# POVD-2.net
KiCad netlist of a schematic drawn in EAGLE
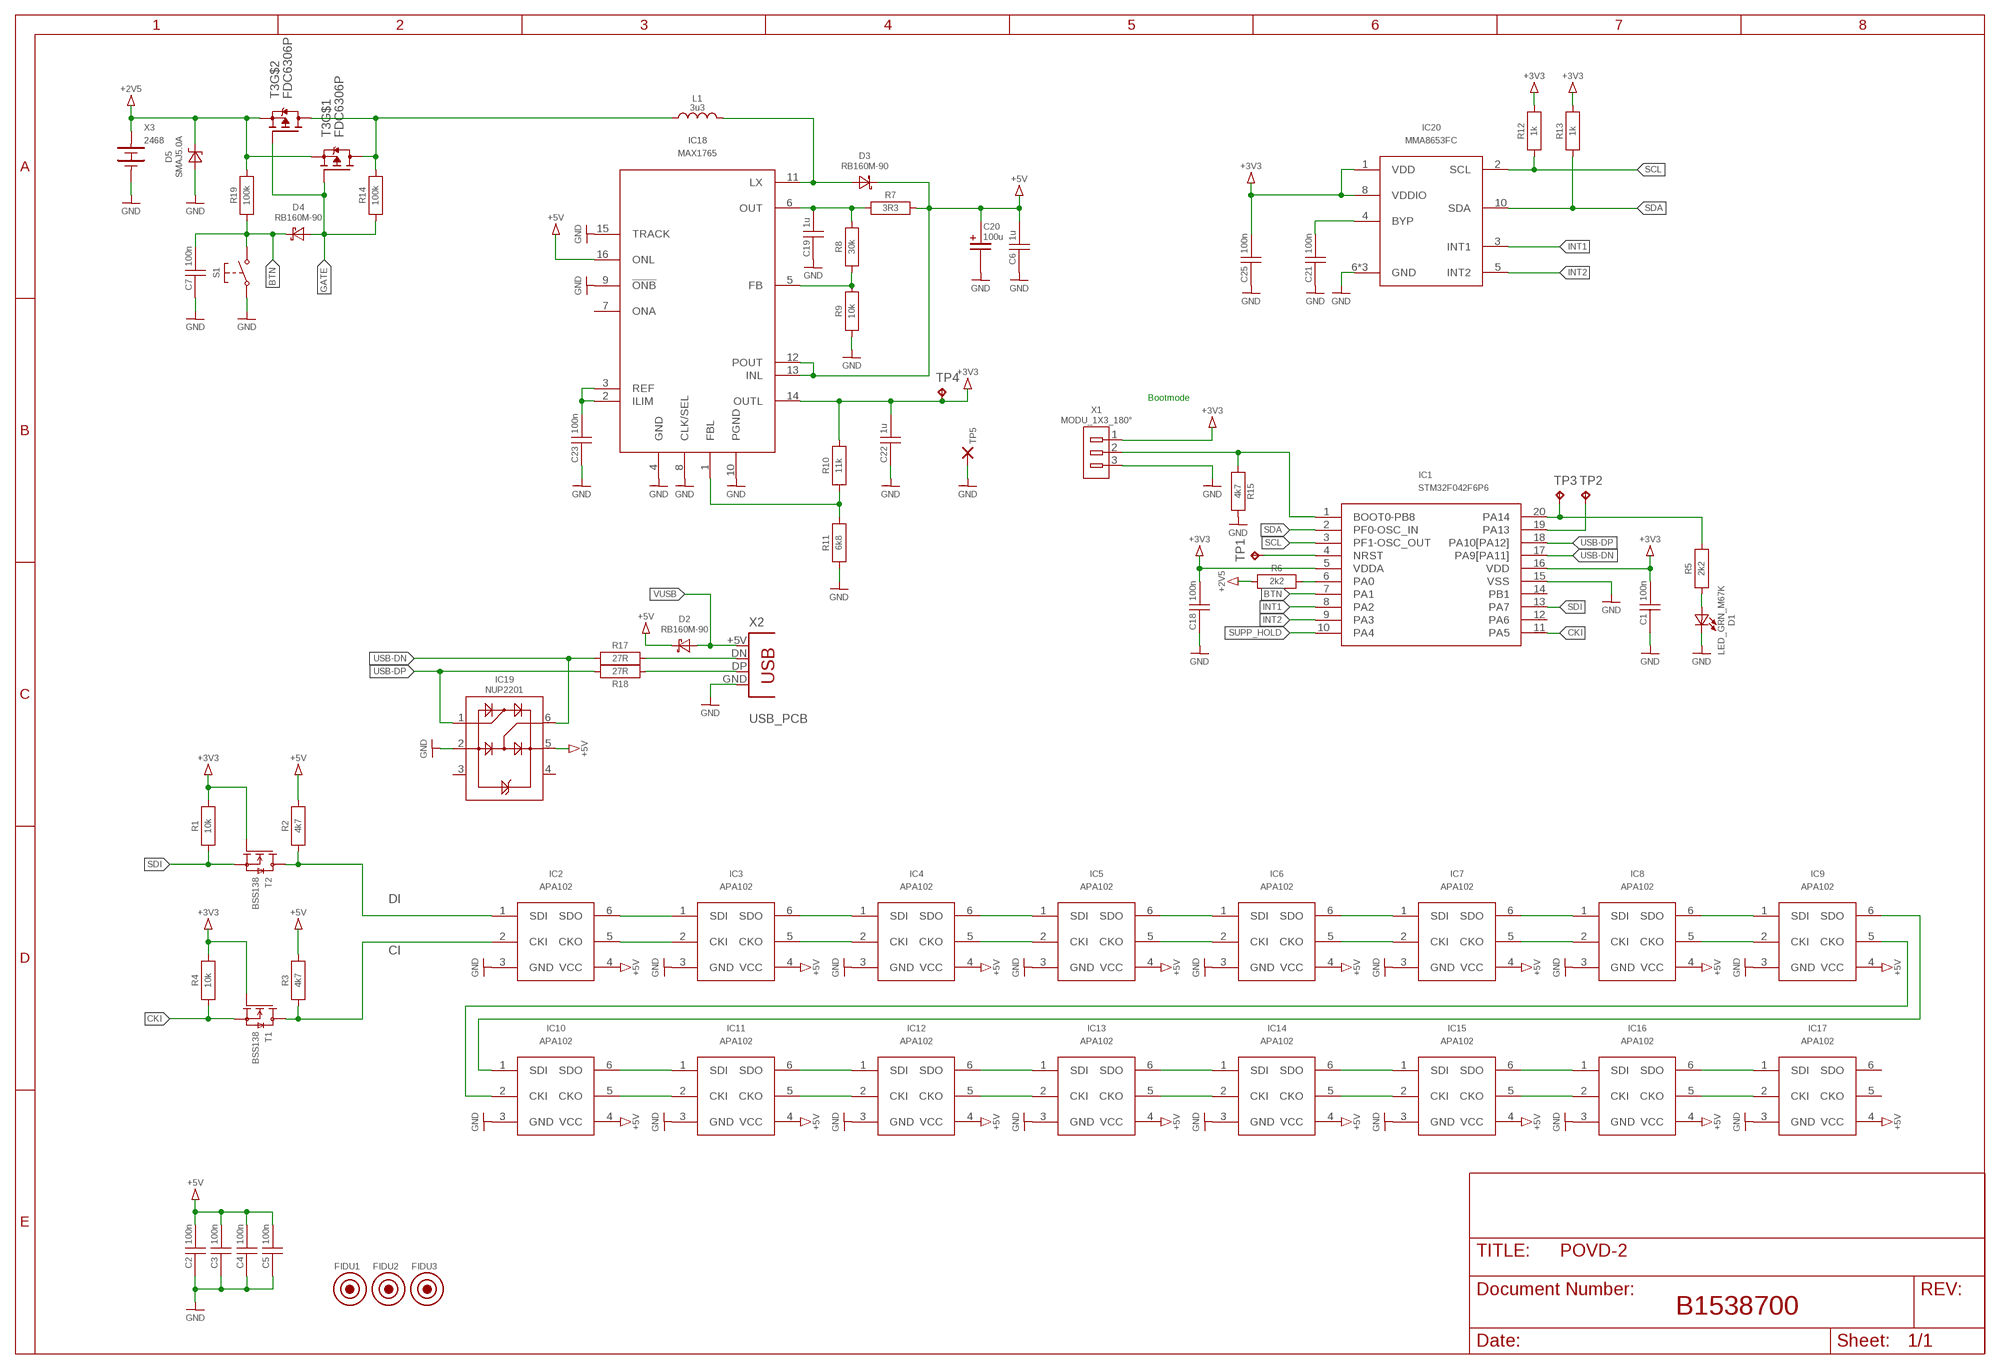
[diagram p0: schematic, sheet 1]

(export (version "E")
  (design (tool "Eeschema 10.0.6"))
  (components
    (comp (ref "C1")
      (value "100n")
      (footprint "eagle-import:SM_1206")
      (fields (field (name "PARTNR") "E0001400"))
      (libsource (lib "eagle-import") (part "C1206"))
    )
    (comp (ref "C2")
      (value "100n")
      (footprint "eagle-import:SM_1206")
      (fields (field (name "PARTNR") "E0001400"))
      (libsource (lib "eagle-import") (part "C1206"))
    )
    (comp (ref "C3")
      (value "100n")
      (footprint "eagle-import:SM_1206")
      (fields (field (name "PARTNR") "E0001400"))
      (libsource (lib "eagle-import") (part "C1206"))
    )
    (comp (ref "C4")
      (value "100n")
      (footprint "eagle-import:SM_1206")
      (fields (field (name "PARTNR") "E0001400"))
      (libsource (lib "eagle-import") (part "C1206"))
    )
    (comp (ref "C5")
      (value "100n")
      (footprint "eagle-import:SM_1206")
      (fields (field (name "PARTNR") "E0001400"))
      (libsource (lib "eagle-import") (part "C1206"))
    )
    (comp (ref "C6")
      (value "1u")
      (footprint "eagle-import:SM_1206")
      (fields (field (name "PARTNR") "E0487200"))
      (libsource (lib "eagle-import") (part "C1206"))
    )
    (comp (ref "C7")
      (value "100n")
      (footprint "eagle-import:SM_1206")
      (fields (field (name "PARTNR") "E0001400"))
      (libsource (lib "eagle-import") (part "C1206"))
    )
    (comp (ref "C18")
      (value "100n")
      (footprint "eagle-import:SM_1206")
      (fields (field (name "PARTNR") "E0001400"))
      (libsource (lib "eagle-import") (part "C1206"))
    )
    (comp (ref "C19")
      (value "1u")
      (footprint "eagle-import:SM_1206")
      (fields (field (name "PARTNR") "E0487200"))
      (libsource (lib "eagle-import") (part "C1206"))
    )
    (comp (ref "C20")
      (value "100u")
      (footprint "eagle-import:SM_SIZE-D")
      (fields (field (name "PARTNR") "E0242200"))
      (libsource (lib "eagle-import") (part "CPOLSIZE-D"))
    )
    (comp (ref "C21")
      (value "100n")
      (footprint "eagle-import:SM_1206")
      (fields (field (name "PARTNR") "E0001400"))
      (libsource (lib "eagle-import") (part "C1206"))
    )
    (comp (ref "C22")
      (value "1u")
      (footprint "eagle-import:SM_1206")
      (fields (field (name "PARTNR") "E0487200"))
      (libsource (lib "eagle-import") (part "C1206"))
    )
    (comp (ref "C23")
      (value "100n")
      (footprint "eagle-import:SM_1206")
      (fields (field (name "PARTNR") "E0001400"))
      (libsource (lib "eagle-import") (part "C1206"))
    )
    (comp (ref "C25")
      (value "100n")
      (footprint "eagle-import:SM_1206")
      (fields (field (name "PARTNR") "E0001400"))
      (libsource (lib "eagle-import") (part "C1206"))
    )
    (comp (ref "D1")
      (value "LED_GRN_M67K")
      (footprint "eagle-import:SM_LED_M67K")
      (libsource (lib "eagle-import") (part "LED_M67K_GRN"))
    )
    (comp (ref "D2")
      (value "RB160M-90")
      (footprint "eagle-import:SM_SOD123_POL")
      (libsource (lib "eagle-import") (part "RB160M-90"))
    )
    (comp (ref "D3")
      (value "RB160M-90")
      (footprint "eagle-import:SM_SOD123_POL")
      (libsource (lib "eagle-import") (part "RB160M-90"))
    )
    (comp (ref "D4")
      (value "RB160M-90")
      (footprint "eagle-import:SM_SOD123_POL")
      (libsource (lib "eagle-import") (part "RB160M-90"))
    )
    (comp (ref "D5")
      (value "SMAJ5.0A")
      (footprint "eagle-import:SM_DO214AC_POL")
      (libsource (lib "eagle-import") (part "SMAJA5.0"))
    )
    (comp (ref "FIDU1")
      (value "FIDU_ROUND_NEW")
      (footprint "eagle-import:FIDUCIAL_LOETSTOPP")
      (libsource (lib "eagle-import") (part "FIDU_ROUND_NEW"))
    )
    (comp (ref "FIDU2")
      (value "FIDU_ROUND_NEW")
      (footprint "eagle-import:FIDUCIAL_LOETSTOPP")
      (libsource (lib "eagle-import") (part "FIDU_ROUND_NEW"))
    )
    (comp (ref "FIDU3")
      (value "FIDU_ROUND_NEW")
      (footprint "eagle-import:FIDUCIAL_LOETSTOPP")
      (libsource (lib "eagle-import") (part "FIDU_ROUND_NEW"))
    )
    (comp (ref "IC1")
      (value "STM32F042F6P6")
      (footprint "eagle-import:SM_TSSOP20")
      (libsource (lib "eagle-import") (part "STM32F042F6P6"))
    )
    (comp (ref "IC2")
      (value "APA102")
      (footprint "eagle-import:SM_LED_PLCC6")
      (libsource (lib "eagle-import") (part "APA102"))
    )
    (comp (ref "IC3")
      (value "APA102")
      (footprint "eagle-import:SM_LED_PLCC6")
      (libsource (lib "eagle-import") (part "APA102"))
    )
    (comp (ref "IC4")
      (value "APA102")
      (footprint "eagle-import:SM_LED_PLCC6")
      (libsource (lib "eagle-import") (part "APA102"))
    )
    (comp (ref "IC5")
      (value "APA102")
      (footprint "eagle-import:SM_LED_PLCC6")
      (libsource (lib "eagle-import") (part "APA102"))
    )
    (comp (ref "IC6")
      (value "APA102")
      (footprint "eagle-import:SM_LED_PLCC6")
      (libsource (lib "eagle-import") (part "APA102"))
    )
    (comp (ref "IC7")
      (value "APA102")
      (footprint "eagle-import:SM_LED_PLCC6")
      (libsource (lib "eagle-import") (part "APA102"))
    )
    (comp (ref "IC8")
      (value "APA102")
      (footprint "eagle-import:SM_LED_PLCC6")
      (libsource (lib "eagle-import") (part "APA102"))
    )
    (comp (ref "IC9")
      (value "APA102")
      (footprint "eagle-import:SM_LED_PLCC6")
      (libsource (lib "eagle-import") (part "APA102"))
    )
    (comp (ref "IC10")
      (value "APA102")
      (footprint "eagle-import:SM_LED_PLCC6")
      (libsource (lib "eagle-import") (part "APA102"))
    )
    (comp (ref "IC11")
      (value "APA102")
      (footprint "eagle-import:SM_LED_PLCC6")
      (libsource (lib "eagle-import") (part "APA102"))
    )
    (comp (ref "IC12")
      (value "APA102")
      (footprint "eagle-import:SM_LED_PLCC6")
      (libsource (lib "eagle-import") (part "APA102"))
    )
    (comp (ref "IC13")
      (value "APA102")
      (footprint "eagle-import:SM_LED_PLCC6")
      (libsource (lib "eagle-import") (part "APA102"))
    )
    (comp (ref "IC14")
      (value "APA102")
      (footprint "eagle-import:SM_LED_PLCC6")
      (libsource (lib "eagle-import") (part "APA102"))
    )
    (comp (ref "IC15")
      (value "APA102")
      (footprint "eagle-import:SM_LED_PLCC6")
      (libsource (lib "eagle-import") (part "APA102"))
    )
    (comp (ref "IC16")
      (value "APA102")
      (footprint "eagle-import:SM_LED_PLCC6")
      (libsource (lib "eagle-import") (part "APA102"))
    )
    (comp (ref "IC17")
      (value "APA102")
      (footprint "eagle-import:SM_LED_PLCC6")
      (libsource (lib "eagle-import") (part "APA102"))
    )
    (comp (ref "IC18")
      (value "MAX1765")
      (footprint "eagle-import:SM_QSOP16")
      (libsource (lib "eagle-import") (part "MAX1765"))
    )
    (comp (ref "IC19")
      (value "NUP2201")
      (footprint "eagle-import:TSOP6")
      (libsource (lib "eagle-import") (part "NUP2201"))
    )
    (comp (ref "IC20")
      (value "MMA8653FC")
      (footprint "eagle-import:SM_DFN10")
      (libsource (lib "eagle-import") (part "MMA8653FC"))
    )
    (comp (ref "L1")
      (value "3u3")
      (footprint "eagle-import:SM_L_MOS6020")
      (libsource (lib "eagle-import") (part "L_MOS6020"))
    )
    (comp (ref "R1")
      (value "10k")
      (footprint "eagle-import:SM_1206")
      (fields (field (name "PARTNR") "E0002700"))
      (libsource (lib "eagle-import") (part "R1206"))
    )
    (comp (ref "R2")
      (value "4k7")
      (footprint "eagle-import:SM_1206")
      (fields (field (name "PARTNR") "E0002200"))
      (libsource (lib "eagle-import") (part "R1206"))
    )
    (comp (ref "R3")
      (value "4k7")
      (footprint "eagle-import:SM_1206")
      (fields (field (name "PARTNR") "E0002200"))
      (libsource (lib "eagle-import") (part "R1206"))
    )
    (comp (ref "R4")
      (value "10k")
      (footprint "eagle-import:SM_1206")
      (fields (field (name "PARTNR") "E0002700"))
      (libsource (lib "eagle-import") (part "R1206"))
    )
    (comp (ref "R5")
      (value "2k2")
      (footprint "eagle-import:SM_1206")
      (fields (field (name "PARTNR") "E0066600"))
      (libsource (lib "eagle-import") (part "R1206"))
    )
    (comp (ref "R6")
      (value "2k2")
      (footprint "eagle-import:SM_1206")
      (fields (field (name "PARTNR") "E0066600"))
      (libsource (lib "eagle-import") (part "R1206"))
    )
    (comp (ref "R7")
      (value "3R3")
      (footprint "eagle-import:SM_1206")
      (fields (field (name "PARTNR") "E0821300"))
      (libsource (lib "eagle-import") (part "R1206"))
    )
    (comp (ref "R8")
      (value "30k")
      (footprint "eagle-import:SM_1206")
      (libsource (lib "eagle-import") (part "R1206"))
    )
    (comp (ref "R9")
      (value "10k")
      (footprint "eagle-import:SM_1206")
      (fields (field (name "PARTNR") "E0002700"))
      (libsource (lib "eagle-import") (part "R1206"))
    )
    (comp (ref "R10")
      (value "11k")
      (footprint "eagle-import:SM_1206")
      (libsource (lib "eagle-import") (part "R1206"))
    )
    (comp (ref "R11")
      (value "6k8")
      (footprint "eagle-import:SM_1206")
      (fields (field (name "PARTNR") "E0195100"))
      (libsource (lib "eagle-import") (part "R1206"))
    )
    (comp (ref "R12")
      (value "1k")
      (footprint "eagle-import:SM_1206")
      (fields (field (name "PARTNR") "E0002500"))
      (libsource (lib "eagle-import") (part "R1206"))
    )
    (comp (ref "R13")
      (value "1k")
      (footprint "eagle-import:SM_1206")
      (fields (field (name "PARTNR") "E0002500"))
      (libsource (lib "eagle-import") (part "R1206"))
    )
    (comp (ref "R14")
      (value "100k")
      (footprint "eagle-import:SM_1206")
      (fields (field (name "PARTNR") "E0002800"))
      (libsource (lib "eagle-import") (part "R1206"))
    )
    (comp (ref "R15")
      (value "4k7")
      (footprint "eagle-import:SM_1206")
      (fields (field (name "PARTNR") "E0002200"))
      (libsource (lib "eagle-import") (part "R1206"))
    )
    (comp (ref "R17")
      (value "27R")
      (footprint "eagle-import:SM_1206")
      (fields (field (name "PARTNR") "E0023100"))
      (libsource (lib "eagle-import") (part "R1206"))
    )
    (comp (ref "R18")
      (value "27R")
      (footprint "eagle-import:SM_1206")
      (fields (field (name "PARTNR") "E0023100"))
      (libsource (lib "eagle-import") (part "R1206"))
    )
    (comp (ref "R19")
      (value "100k")
      (footprint "eagle-import:SM_1206")
      (fields (field (name "PARTNR") "E0002800"))
      (libsource (lib "eagle-import") (part "R1206"))
    )
    (comp (ref "S1")
      (value "PUSH-BUTTON_SMD")
      (footprint "eagle-import:PUSH-BUTTON_SMD")
      (libsource (lib "eagle-import") (part "PUSH-BUTTON_SMD"))
    )
    (comp (ref "T1")
      (value "BSS138")
      (footprint "eagle-import:SM_SOT23")
      (libsource (lib "eagle-import") (part "BSS138"))
    )
    (comp (ref "T2")
      (value "BSS138")
      (footprint "eagle-import:SM_SOT23")
      (libsource (lib "eagle-import") (part "BSS138"))
    )
    (comp (ref "T3")
      (value "FDC6306P")
      (footprint "eagle-import:TSOP6")
      (fields (field (name "PARTNR") "E0662100"))
      (libsource (lib "eagle-import") (part "FDC6306P"))
    )
    (comp (ref "TP1")
      (value "TPTP12R")
      (footprint "eagle-import:TP12R")
      (libsource (lib "eagle-import") (part "TPTP12R"))
    )
    (comp (ref "TP2")
      (value "TPTP12R")
      (footprint "eagle-import:TP12R")
      (libsource (lib "eagle-import") (part "TPTP12R"))
    )
    (comp (ref "TP3")
      (value "TPTP12R")
      (footprint "eagle-import:TP12R")
      (libsource (lib "eagle-import") (part "TPTP12R"))
    )
    (comp (ref "TP4")
      (value "TPTP12R")
      (footprint "eagle-import:TP12R")
      (libsource (lib "eagle-import") (part "TPTP12R"))
    )
    (comp (ref "TP5")
      (value "CHECKER_1206")
      (footprint "eagle-import:SM_RCW_1206")
      (libsource (lib "eagle-import") (part "CHECKER_1206"))
    )
    (comp (ref "X1")
      (value "MODU_1X3_180°")
      (footprint "eagle-import:MODU_3X1_180°")
      (libsource (lib "eagle-import") (part "MODU_1X3_180°"))
    )
    (comp (ref "X2")
      (value "USB_PCB")
      (footprint "eagle-import:USB_PCB")
      (libsource (lib "eagle-import") (part "USB_PCB"))
    )
    (comp (ref "X3")
      (value "2468")
      (footprint "eagle-import:2468")
      (libsource (lib "eagle-import") (part "2468"))
    )
  )
  (nets
    (net (code "1") (name "+2V5") (class "Default")
      (node (ref "D5") (pin "C") (pinfunction "C_C") (pintype "bidirectional"))
      (node (ref "R19") (pin "2") (pinfunction "2_2") (pintype "bidirectional"))
      (node (ref "R6") (pin "2") (pinfunction "2_2") (pintype "bidirectional"))
      (node (ref "T3") (pin "2") (pinfunction "S_2") (pintype "passive"))
      (node (ref "T3") (pin "5") (pinfunction "S_5") (pintype "passive"))
      (node (ref "X3") (pin "POS") (pinfunction "POS_POS") (pintype "bidirectional"))
    )
    (net (code "2") (name "+3V3") (class "Default")
      (node (ref "C1") (pin "2") (pinfunction "2_2") (pintype "bidirectional"))
      (node (ref "C18") (pin "2") (pinfunction "2_2") (pintype "bidirectional"))
      (node (ref "C22") (pin "2") (pinfunction "2_2") (pintype "bidirectional"))
      (node (ref "C25") (pin "2") (pinfunction "2_2") (pintype "bidirectional"))
      (node (ref "IC1") (pin "16") (pinfunction "VDD_16") (pintype "bidirectional"))
      (node (ref "IC1") (pin "5") (pinfunction "VDDA_5") (pintype "bidirectional"))
      (node (ref "IC18") (pin "14") (pinfunction "OUTL_14") (pintype "bidirectional"))
      (node (ref "IC20") (pin "1") (pinfunction "VDD_1") (pintype "bidirectional"))
      (node (ref "IC20") (pin "8") (pinfunction "VDDIO_8") (pintype "bidirectional"))
      (node (ref "R1") (pin "2") (pinfunction "2_2") (pintype "bidirectional"))
      (node (ref "R10") (pin "2") (pinfunction "2_2") (pintype "bidirectional"))
      (node (ref "R12") (pin "2") (pinfunction "2_2") (pintype "bidirectional"))
      (node (ref "R13") (pin "2") (pinfunction "2_2") (pintype "bidirectional"))
      (node (ref "R4") (pin "2") (pinfunction "2_2") (pintype "bidirectional"))
      (node (ref "T1") (pin "1") (pinfunction "G_1") (pintype "bidirectional"))
      (node (ref "T2") (pin "1") (pinfunction "G_1") (pintype "bidirectional"))
      (node (ref "TP4") (pin "TP") (pinfunction "TP_TP") (pintype "input"))
      (node (ref "X1") (pin "1") (pinfunction "1_1") (pintype "bidirectional"))
    )
    (net (code "3") (name "+5V") (class "Default")
      (node (ref "C2") (pin "2") (pinfunction "2_2") (pintype "bidirectional"))
      (node (ref "C20") (pin "POS") (pinfunction "POS_POS") (pintype "bidirectional"))
      (node (ref "C3") (pin "2") (pinfunction "2_2") (pintype "bidirectional"))
      (node (ref "C4") (pin "2") (pinfunction "2_2") (pintype "bidirectional"))
      (node (ref "C5") (pin "2") (pinfunction "2_2") (pintype "bidirectional"))
      (node (ref "C6") (pin "2") (pinfunction "2_2") (pintype "bidirectional"))
      (node (ref "D2") (pin "C") (pinfunction "C_C") (pintype "bidirectional"))
      (node (ref "D3") (pin "C") (pinfunction "C_C") (pintype "bidirectional"))
      (node (ref "IC10") (pin "4") (pinfunction "VCC_4") (pintype "bidirectional"))
      (node (ref "IC11") (pin "4") (pinfunction "VCC_4") (pintype "bidirectional"))
      (node (ref "IC12") (pin "4") (pinfunction "VCC_4") (pintype "bidirectional"))
      (node (ref "IC13") (pin "4") (pinfunction "VCC_4") (pintype "bidirectional"))
      (node (ref "IC14") (pin "4") (pinfunction "VCC_4") (pintype "bidirectional"))
      (node (ref "IC15") (pin "4") (pinfunction "VCC_4") (pintype "bidirectional"))
      (node (ref "IC16") (pin "4") (pinfunction "VCC_4") (pintype "bidirectional"))
      (node (ref "IC17") (pin "4") (pinfunction "VCC_4") (pintype "bidirectional"))
      (node (ref "IC18") (pin "12") (pinfunction "POUT_12") (pintype "bidirectional"))
      (node (ref "IC18") (pin "13") (pinfunction "INL_13") (pintype "bidirectional"))
      (node (ref "IC18") (pin "16") (pinfunction "ONL_16") (pintype "bidirectional"))
      (node (ref "IC19") (pin "5") (pinfunction "VP_5") (pintype "bidirectional"))
      (node (ref "IC2") (pin "4") (pinfunction "VCC_4") (pintype "bidirectional"))
      (node (ref "IC3") (pin "4") (pinfunction "VCC_4") (pintype "bidirectional"))
      (node (ref "IC4") (pin "4") (pinfunction "VCC_4") (pintype "bidirectional"))
      (node (ref "IC5") (pin "4") (pinfunction "VCC_4") (pintype "bidirectional"))
      (node (ref "IC6") (pin "4") (pinfunction "VCC_4") (pintype "bidirectional"))
      (node (ref "IC7") (pin "4") (pinfunction "VCC_4") (pintype "bidirectional"))
      (node (ref "IC8") (pin "4") (pinfunction "VCC_4") (pintype "bidirectional"))
      (node (ref "IC9") (pin "4") (pinfunction "VCC_4") (pintype "bidirectional"))
      (node (ref "R2") (pin "2") (pinfunction "2_2") (pintype "bidirectional"))
      (node (ref "R3") (pin "2") (pinfunction "2_2") (pintype "bidirectional"))
      (node (ref "R7") (pin "2") (pinfunction "2_2") (pintype "bidirectional"))
    )
    (net (code "4") (name "/CI") (class "Default")
      (node (ref "IC2") (pin "2") (pinfunction "CKI_2") (pintype "bidirectional"))
      (node (ref "R3") (pin "1") (pinfunction "1_1") (pintype "bidirectional"))
      (node (ref "T1") (pin "3") (pinfunction "D_3") (pintype "bidirectional"))
    )
    (net (code "5") (name "/DI") (class "Default")
      (node (ref "IC2") (pin "1") (pinfunction "SDI_1") (pintype "bidirectional"))
      (node (ref "R2") (pin "1") (pinfunction "1_1") (pintype "bidirectional"))
      (node (ref "T2") (pin "3") (pinfunction "D_3") (pintype "bidirectional"))
    )
    (net (code "6") (name "BTN") (class "Default")
      (node (ref "C7") (pin "2") (pinfunction "2_2") (pintype "bidirectional"))
      (node (ref "D4") (pin "C") (pinfunction "C_C") (pintype "bidirectional"))
      (node (ref "IC1") (pin "7") (pinfunction "PA1_7") (pintype "bidirectional"))
      (node (ref "R19") (pin "1") (pinfunction "1_1") (pintype "bidirectional"))
      (node (ref "S1") (pin "3") (pinfunction "S_3") (pintype "passive"))
      (node (ref "S1") (pin "4") (pinfunction "S_4") (pintype "passive"))
    )
    (net (code "7") (name "CKI") (class "Default")
      (node (ref "IC1") (pin "11") (pinfunction "PA5_11") (pintype "bidirectional"))
      (node (ref "R4") (pin "1") (pinfunction "1_1") (pintype "bidirectional"))
      (node (ref "T1") (pin "2") (pinfunction "S_2") (pintype "bidirectional"))
    )
    (net (code "8") (name "GATE") (class "Default")
      (node (ref "D4") (pin "A") (pinfunction "A_A") (pintype "bidirectional"))
      (node (ref "R14") (pin "1") (pinfunction "1_1") (pintype "bidirectional"))
      (node (ref "T3") (pin "1") (pinfunction "G_1") (pintype "passive"))
      (node (ref "T3") (pin "3") (pinfunction "G_3") (pintype "passive"))
    )
    (net (code "9") (name "GND") (class "Default")
      (node (ref "C1") (pin "1") (pinfunction "1_1") (pintype "bidirectional"))
      (node (ref "C18") (pin "1") (pinfunction "1_1") (pintype "bidirectional"))
      (node (ref "C19") (pin "1") (pinfunction "1_1") (pintype "bidirectional"))
      (node (ref "C2") (pin "1") (pinfunction "1_1") (pintype "bidirectional"))
      (node (ref "C20") (pin "NEG") (pinfunction "NEG_NEG") (pintype "bidirectional"))
      (node (ref "C21") (pin "1") (pinfunction "1_1") (pintype "bidirectional"))
      (node (ref "C22") (pin "1") (pinfunction "1_1") (pintype "bidirectional"))
      (node (ref "C23") (pin "1") (pinfunction "1_1") (pintype "bidirectional"))
      (node (ref "C25") (pin "1") (pinfunction "1_1") (pintype "bidirectional"))
      (node (ref "C3") (pin "1") (pinfunction "1_1") (pintype "bidirectional"))
      (node (ref "C4") (pin "1") (pinfunction "1_1") (pintype "bidirectional"))
      (node (ref "C5") (pin "1") (pinfunction "1_1") (pintype "bidirectional"))
      (node (ref "C6") (pin "1") (pinfunction "1_1") (pintype "bidirectional"))
      (node (ref "C7") (pin "1") (pinfunction "1_1") (pintype "bidirectional"))
      (node (ref "D1") (pin "C") (pinfunction "C_C") (pintype "passive"))
      (node (ref "D5") (pin "A") (pinfunction "A_A") (pintype "bidirectional"))
      (node (ref "IC1") (pin "15") (pinfunction "VSS_15") (pintype "bidirectional"))
      (node (ref "IC10") (pin "3") (pinfunction "GND_3") (pintype "bidirectional"))
      (node (ref "IC11") (pin "3") (pinfunction "GND_3") (pintype "bidirectional"))
      (node (ref "IC12") (pin "3") (pinfunction "GND_3") (pintype "bidirectional"))
      (node (ref "IC13") (pin "3") (pinfunction "GND_3") (pintype "bidirectional"))
      (node (ref "IC14") (pin "3") (pinfunction "GND_3") (pintype "bidirectional"))
      (node (ref "IC15") (pin "3") (pinfunction "GND_3") (pintype "bidirectional"))
      (node (ref "IC16") (pin "3") (pinfunction "GND_3") (pintype "bidirectional"))
      (node (ref "IC17") (pin "3") (pinfunction "GND_3") (pintype "bidirectional"))
      (node (ref "IC18") (pin "10") (pinfunction "PGND_10") (pintype "bidirectional"))
      (node (ref "IC18") (pin "15") (pinfunction "TRACK_15") (pintype "bidirectional"))
      (node (ref "IC18") (pin "4") (pinfunction "GND_4") (pintype "bidirectional"))
      (node (ref "IC18") (pin "8") (pinfunction "CLK/SEL_8") (pintype "bidirectional"))
      (node (ref "IC18") (pin "9") (pinfunction "~{ONB}_9") (pintype "bidirectional"))
      (node (ref "IC19") (pin "2") (pinfunction "GND_2") (pintype "bidirectional"))
      (node (ref "IC2") (pin "3") (pinfunction "GND_3") (pintype "bidirectional"))
      (node (ref "IC20") (pin "6") (pinfunction "GND_6") (pintype "bidirectional"))
      (node (ref "IC20") (pin "7") (pinfunction "GND_7") (pintype "bidirectional"))
      (node (ref "IC20") (pin "9") (pinfunction "GND_9") (pintype "bidirectional"))
      (node (ref "IC3") (pin "3") (pinfunction "GND_3") (pintype "bidirectional"))
      (node (ref "IC4") (pin "3") (pinfunction "GND_3") (pintype "bidirectional"))
      (node (ref "IC5") (pin "3") (pinfunction "GND_3") (pintype "bidirectional"))
      (node (ref "IC6") (pin "3") (pinfunction "GND_3") (pintype "bidirectional"))
      (node (ref "IC7") (pin "3") (pinfunction "GND_3") (pintype "bidirectional"))
      (node (ref "IC8") (pin "3") (pinfunction "GND_3") (pintype "bidirectional"))
      (node (ref "IC9") (pin "3") (pinfunction "GND_3") (pintype "bidirectional"))
      (node (ref "R11") (pin "1") (pinfunction "1_1") (pintype "bidirectional"))
      (node (ref "R15") (pin "2") (pinfunction "2_2") (pintype "bidirectional"))
      (node (ref "R9") (pin "1") (pinfunction "1_1") (pintype "bidirectional"))
      (node (ref "S1") (pin "1") (pinfunction "P_1") (pintype "passive"))
      (node (ref "S1") (pin "2") (pinfunction "P_2") (pintype "passive"))
      (node (ref "TP5") (pin "1") (pinfunction "P_1") (pintype "passive"))
      (node (ref "X1") (pin "3") (pinfunction "3_3") (pintype "bidirectional"))
      (node (ref "X2") (pin "GND") (pinfunction "GND_GND") (pintype "passive"))
      (node (ref "X3") (pin "NEG") (pinfunction "NEG_NEG") (pintype "bidirectional"))
    )
    (net (code "10") (name "INT1") (class "Default")
      (node (ref "IC1") (pin "8") (pinfunction "PA2_8") (pintype "bidirectional"))
      (node (ref "IC20") (pin "3") (pinfunction "INT1_3") (pintype "bidirectional"))
    )
    (net (code "11") (name "INT2") (class "Default")
      (node (ref "IC1") (pin "9") (pinfunction "PA3_9") (pintype "bidirectional"))
      (node (ref "IC20") (pin "5") (pinfunction "INT2_5") (pintype "bidirectional"))
    )
    (net (code "12") (name "Net-(D1-PadA)") (class "Default")
      (node (ref "D1") (pin "A") (pinfunction "A_A") (pintype "passive"))
      (node (ref "R5") (pin "1") (pinfunction "1_1") (pintype "bidirectional"))
    )
    (net (code "13") (name "Net-(IC1-BOOT0-PB8)") (class "Default")
      (node (ref "IC1") (pin "1") (pinfunction "BOOT0-PB8_1") (pintype "bidirectional"))
      (node (ref "R15") (pin "1") (pinfunction "1_1") (pintype "bidirectional"))
      (node (ref "X1") (pin "2") (pinfunction "2_2") (pintype "bidirectional"))
    )
    (net (code "14") (name "Net-(IC1-NRST)") (class "Default")
      (node (ref "IC1") (pin "4") (pinfunction "NRST_4") (pintype "bidirectional"))
      (node (ref "TP1") (pin "TP") (pinfunction "TP_TP") (pintype "input"))
    )
    (net (code "15") (name "Net-(IC1-PA0)") (class "Default")
      (node (ref "IC1") (pin "6") (pinfunction "PA0_6") (pintype "bidirectional"))
      (node (ref "R6") (pin "1") (pinfunction "1_1") (pintype "bidirectional"))
    )
    (net (code "16") (name "Net-(IC1-PA13)") (class "Default")
      (node (ref "IC1") (pin "19") (pinfunction "PA13_19") (pintype "bidirectional"))
      (node (ref "TP2") (pin "TP") (pinfunction "TP_TP") (pintype "input"))
    )
    (net (code "17") (name "Net-(IC1-PA14)") (class "Default")
      (node (ref "IC1") (pin "20") (pinfunction "PA14_20") (pintype "bidirectional"))
      (node (ref "R5") (pin "2") (pinfunction "2_2") (pintype "bidirectional"))
      (node (ref "TP3") (pin "TP") (pinfunction "TP_TP") (pintype "input"))
    )
    (net (code "18") (name "Net-(IC2-CKO)") (class "Default")
      (node (ref "IC2") (pin "5") (pinfunction "CKO_5") (pintype "bidirectional"))
      (node (ref "IC3") (pin "2") (pinfunction "CKI_2") (pintype "bidirectional"))
    )
    (net (code "19") (name "Net-(IC2-SDO)") (class "Default")
      (node (ref "IC2") (pin "6") (pinfunction "SDO_6") (pintype "bidirectional"))
      (node (ref "IC3") (pin "1") (pinfunction "SDI_1") (pintype "bidirectional"))
    )
    (net (code "20") (name "Net-(IC3-CKO)") (class "Default")
      (node (ref "IC3") (pin "5") (pinfunction "CKO_5") (pintype "bidirectional"))
      (node (ref "IC4") (pin "2") (pinfunction "CKI_2") (pintype "bidirectional"))
    )
    (net (code "21") (name "Net-(IC3-SDO)") (class "Default")
      (node (ref "IC3") (pin "6") (pinfunction "SDO_6") (pintype "bidirectional"))
      (node (ref "IC4") (pin "1") (pinfunction "SDI_1") (pintype "bidirectional"))
    )
    (net (code "22") (name "Net-(IC4-CKO)") (class "Default")
      (node (ref "IC4") (pin "5") (pinfunction "CKO_5") (pintype "bidirectional"))
      (node (ref "IC5") (pin "2") (pinfunction "CKI_2") (pintype "bidirectional"))
    )
    (net (code "23") (name "Net-(IC4-SDO)") (class "Default")
      (node (ref "IC4") (pin "6") (pinfunction "SDO_6") (pintype "bidirectional"))
      (node (ref "IC5") (pin "1") (pinfunction "SDI_1") (pintype "bidirectional"))
    )
    (net (code "24") (name "Net-(IC5-CKO)") (class "Default")
      (node (ref "IC5") (pin "5") (pinfunction "CKO_5") (pintype "bidirectional"))
      (node (ref "IC6") (pin "2") (pinfunction "CKI_2") (pintype "bidirectional"))
    )
    (net (code "25") (name "Net-(IC5-SDO)") (class "Default")
      (node (ref "IC5") (pin "6") (pinfunction "SDO_6") (pintype "bidirectional"))
      (node (ref "IC6") (pin "1") (pinfunction "SDI_1") (pintype "bidirectional"))
    )
    (net (code "26") (name "Net-(IC6-CKO)") (class "Default")
      (node (ref "IC6") (pin "5") (pinfunction "CKO_5") (pintype "bidirectional"))
      (node (ref "IC7") (pin "2") (pinfunction "CKI_2") (pintype "bidirectional"))
    )
    (net (code "27") (name "Net-(IC6-SDO)") (class "Default")
      (node (ref "IC6") (pin "6") (pinfunction "SDO_6") (pintype "bidirectional"))
      (node (ref "IC7") (pin "1") (pinfunction "SDI_1") (pintype "bidirectional"))
    )
    (net (code "28") (name "Net-(IC7-CKO)") (class "Default")
      (node (ref "IC7") (pin "5") (pinfunction "CKO_5") (pintype "bidirectional"))
      (node (ref "IC8") (pin "2") (pinfunction "CKI_2") (pintype "bidirectional"))
    )
    (net (code "29") (name "Net-(IC7-SDO)") (class "Default")
      (node (ref "IC7") (pin "6") (pinfunction "SDO_6") (pintype "bidirectional"))
      (node (ref "IC8") (pin "1") (pinfunction "SDI_1") (pintype "bidirectional"))
    )
    (net (code "30") (name "Net-(IC8-CKO)") (class "Default")
      (node (ref "IC8") (pin "5") (pinfunction "CKO_5") (pintype "bidirectional"))
      (node (ref "IC9") (pin "2") (pinfunction "CKI_2") (pintype "bidirectional"))
    )
    (net (code "31") (name "Net-(IC8-SDO)") (class "Default")
      (node (ref "IC8") (pin "6") (pinfunction "SDO_6") (pintype "bidirectional"))
      (node (ref "IC9") (pin "1") (pinfunction "SDI_1") (pintype "bidirectional"))
    )
    (net (code "32") (name "Net-(IC10-CKI)") (class "Default")
      (node (ref "IC10") (pin "2") (pinfunction "CKI_2") (pintype "bidirectional"))
      (node (ref "IC9") (pin "5") (pinfunction "CKO_5") (pintype "bidirectional"))
    )
    (net (code "33") (name "Net-(IC10-CKO)") (class "Default")
      (node (ref "IC10") (pin "5") (pinfunction "CKO_5") (pintype "bidirectional"))
      (node (ref "IC11") (pin "2") (pinfunction "CKI_2") (pintype "bidirectional"))
    )
    (net (code "34") (name "Net-(IC10-SDI)") (class "Default")
      (node (ref "IC10") (pin "1") (pinfunction "SDI_1") (pintype "bidirectional"))
      (node (ref "IC9") (pin "6") (pinfunction "SDO_6") (pintype "bidirectional"))
    )
    (net (code "35") (name "Net-(IC10-SDO)") (class "Default")
      (node (ref "IC10") (pin "6") (pinfunction "SDO_6") (pintype "bidirectional"))
      (node (ref "IC11") (pin "1") (pinfunction "SDI_1") (pintype "bidirectional"))
    )
    (net (code "36") (name "Net-(IC11-CKO)") (class "Default")
      (node (ref "IC11") (pin "5") (pinfunction "CKO_5") (pintype "bidirectional"))
      (node (ref "IC12") (pin "2") (pinfunction "CKI_2") (pintype "bidirectional"))
    )
    (net (code "37") (name "Net-(IC11-SDO)") (class "Default")
      (node (ref "IC11") (pin "6") (pinfunction "SDO_6") (pintype "bidirectional"))
      (node (ref "IC12") (pin "1") (pinfunction "SDI_1") (pintype "bidirectional"))
    )
    (net (code "38") (name "Net-(IC12-CKO)") (class "Default")
      (node (ref "IC12") (pin "5") (pinfunction "CKO_5") (pintype "bidirectional"))
      (node (ref "IC13") (pin "2") (pinfunction "CKI_2") (pintype "bidirectional"))
    )
    (net (code "39") (name "Net-(IC12-SDO)") (class "Default")
      (node (ref "IC12") (pin "6") (pinfunction "SDO_6") (pintype "bidirectional"))
      (node (ref "IC13") (pin "1") (pinfunction "SDI_1") (pintype "bidirectional"))
    )
    (net (code "40") (name "Net-(IC13-CKO)") (class "Default")
      (node (ref "IC13") (pin "5") (pinfunction "CKO_5") (pintype "bidirectional"))
      (node (ref "IC14") (pin "2") (pinfunction "CKI_2") (pintype "bidirectional"))
    )
    (net (code "41") (name "Net-(IC13-SDO)") (class "Default")
      (node (ref "IC13") (pin "6") (pinfunction "SDO_6") (pintype "bidirectional"))
      (node (ref "IC14") (pin "1") (pinfunction "SDI_1") (pintype "bidirectional"))
    )
    (net (code "42") (name "Net-(IC14-CKO)") (class "Default")
      (node (ref "IC14") (pin "5") (pinfunction "CKO_5") (pintype "bidirectional"))
      (node (ref "IC15") (pin "2") (pinfunction "CKI_2") (pintype "bidirectional"))
    )
    (net (code "43") (name "Net-(IC14-SDO)") (class "Default")
      (node (ref "IC14") (pin "6") (pinfunction "SDO_6") (pintype "bidirectional"))
      (node (ref "IC15") (pin "1") (pinfunction "SDI_1") (pintype "bidirectional"))
    )
    (net (code "44") (name "Net-(IC15-CKO)") (class "Default")
      (node (ref "IC15") (pin "5") (pinfunction "CKO_5") (pintype "bidirectional"))
      (node (ref "IC16") (pin "2") (pinfunction "CKI_2") (pintype "bidirectional"))
    )
    (net (code "45") (name "Net-(IC15-SDO)") (class "Default")
      (node (ref "IC15") (pin "6") (pinfunction "SDO_6") (pintype "bidirectional"))
      (node (ref "IC16") (pin "1") (pinfunction "SDI_1") (pintype "bidirectional"))
    )
    (net (code "46") (name "Net-(IC16-CKO)") (class "Default")
      (node (ref "IC16") (pin "5") (pinfunction "CKO_5") (pintype "bidirectional"))
      (node (ref "IC17") (pin "2") (pinfunction "CKI_2") (pintype "bidirectional"))
    )
    (net (code "47") (name "Net-(IC16-SDO)") (class "Default")
      (node (ref "IC16") (pin "6") (pinfunction "SDO_6") (pintype "bidirectional"))
      (node (ref "IC17") (pin "1") (pinfunction "SDI_1") (pintype "bidirectional"))
    )
    (net (code "48") (name "Net-(IC18-FB)") (class "Default")
      (node (ref "IC18") (pin "5") (pinfunction "FB_5") (pintype "bidirectional"))
      (node (ref "R8") (pin "1") (pinfunction "1_1") (pintype "bidirectional"))
      (node (ref "R9") (pin "2") (pinfunction "2_2") (pintype "bidirectional"))
    )
    (net (code "49") (name "Net-(IC18-FBL)") (class "Default")
      (node (ref "IC18") (pin "1") (pinfunction "FBL_1") (pintype "bidirectional"))
      (node (ref "R10") (pin "1") (pinfunction "1_1") (pintype "bidirectional"))
      (node (ref "R11") (pin "2") (pinfunction "2_2") (pintype "bidirectional"))
    )
    (net (code "50") (name "Net-(IC18-ILIM)") (class "Default")
      (node (ref "C23") (pin "2") (pinfunction "2_2") (pintype "bidirectional"))
      (node (ref "IC18") (pin "2") (pinfunction "ILIM_2") (pintype "bidirectional"))
      (node (ref "IC18") (pin "3") (pinfunction "REF_3") (pintype "bidirectional"))
    )
    (net (code "51") (name "Net-(IC18-LX)") (class "Default")
      (node (ref "D3") (pin "A") (pinfunction "A_A") (pintype "bidirectional"))
      (node (ref "IC18") (pin "11") (pinfunction "LX_11") (pintype "bidirectional"))
      (node (ref "L1") (pin "2") (pinfunction "2_2") (pintype "bidirectional"))
    )
    (net (code "52") (name "Net-(IC18-OUT)") (class "Default")
      (node (ref "C19") (pin "2") (pinfunction "2_2") (pintype "bidirectional"))
      (node (ref "IC18") (pin "6") (pinfunction "OUT_6") (pintype "bidirectional"))
      (node (ref "R7") (pin "1") (pinfunction "1_1") (pintype "bidirectional"))
      (node (ref "R8") (pin "2") (pinfunction "2_2") (pintype "bidirectional"))
    )
    (net (code "53") (name "Net-(IC20-BYP)") (class "Default")
      (node (ref "C21") (pin "2") (pinfunction "2_2") (pintype "bidirectional"))
      (node (ref "IC20") (pin "4") (pinfunction "BYP_4") (pintype "bidirectional"))
    )
    (net (code "54") (name "Net-(R17-Pad2)") (class "Default")
      (node (ref "R17") (pin "2") (pinfunction "2_2") (pintype "bidirectional"))
      (node (ref "X2") (pin "DN") (pinfunction "DN_DN") (pintype "passive"))
    )
    (net (code "55") (name "Net-(R18-Pad1)") (class "Default")
      (node (ref "R18") (pin "1") (pinfunction "1_1") (pintype "bidirectional"))
      (node (ref "X2") (pin "DP") (pinfunction "DP_DP") (pintype "passive"))
    )
    (net (code "56") (name "Net-(T3A-D)") (class "Default")
      (node (ref "L1") (pin "1") (pinfunction "1_1") (pintype "bidirectional"))
      (node (ref "R14") (pin "2") (pinfunction "2_2") (pintype "bidirectional"))
      (node (ref "T3") (pin "4") (pinfunction "D_4") (pintype "passive"))
      (node (ref "T3") (pin "6") (pinfunction "D_6") (pintype "passive"))
    )
    (net (code "57") (name "SCL") (class "Default")
      (node (ref "IC1") (pin "3") (pinfunction "PF1-OSC_OUT_3") (pintype "bidirectional"))
      (node (ref "IC20") (pin "2") (pinfunction "SCL_2") (pintype "bidirectional"))
      (node (ref "R12") (pin "1") (pinfunction "1_1") (pintype "bidirectional"))
    )
    (net (code "58") (name "SDA") (class "Default")
      (node (ref "IC1") (pin "2") (pinfunction "PF0-OSC_IN_2") (pintype "bidirectional"))
      (node (ref "IC20") (pin "10") (pinfunction "SDA_10") (pintype "bidirectional"))
      (node (ref "R13") (pin "1") (pinfunction "1_1") (pintype "bidirectional"))
    )
    (net (code "59") (name "SDI") (class "Default")
      (node (ref "IC1") (pin "13") (pinfunction "PA7_13") (pintype "bidirectional"))
      (node (ref "R1") (pin "1") (pinfunction "1_1") (pintype "bidirectional"))
      (node (ref "T2") (pin "2") (pinfunction "S_2") (pintype "bidirectional"))
    )
    (net (code "60") (name "SUPP_HOLD") (class "Default")
      (node (ref "IC1") (pin "10") (pinfunction "PA4_10") (pintype "bidirectional"))
    )
    (net (code "61") (name "USB-DN") (class "Default")
      (node (ref "IC1") (pin "17") (pinfunction "PA9[PA11]_17") (pintype "bidirectional"))
      (node (ref "IC19") (pin "6") (pinfunction "IO2_6") (pintype "bidirectional"))
      (node (ref "R17") (pin "1") (pinfunction "1_1") (pintype "bidirectional"))
    )
    (net (code "62") (name "USB-DP") (class "Default")
      (node (ref "IC1") (pin "18") (pinfunction "PA10[PA12]_18") (pintype "bidirectional"))
      (node (ref "IC19") (pin "1") (pinfunction "IO1_1") (pintype "bidirectional"))
      (node (ref "R18") (pin "2") (pinfunction "2_2") (pintype "bidirectional"))
    )
    (net (code "63") (name "VUSB") (class "Default")
      (node (ref "D2") (pin "A") (pinfunction "A_A") (pintype "bidirectional"))
      (node (ref "X2") (pin "+5V") (pinfunction "+5V_+5V") (pintype "passive"))
    )
    (net (code "64") (name "unconnected-(IC1-PA6-Pad12)") (class "Default")
      (node (ref "IC1") (pin "12") (pinfunction "PA6_12") (pintype "bidirectional"))
    )
    (net (code "65") (name "unconnected-(IC1-PB1-Pad14)") (class "Default")
      (node (ref "IC1") (pin "14") (pinfunction "PB1_14") (pintype "bidirectional"))
    )
    (net (code "66") (name "unconnected-(IC17-CKO-Pad5)") (class "Default")
      (node (ref "IC17") (pin "5") (pinfunction "CKO_5") (pintype "bidirectional"))
    )
    (net (code "67") (name "unconnected-(IC17-SDO-Pad6)") (class "Default")
      (node (ref "IC17") (pin "6") (pinfunction "SDO_6") (pintype "bidirectional"))
    )
    (net (code "68") (name "unconnected-(IC18-ONA-Pad7)") (class "Default")
      (node (ref "IC18") (pin "7") (pinfunction "ONA_7") (pintype "bidirectional"))
    )
    (net (code "69") (name "unconnected-(IC19-NC1-Pad3)") (class "Default")
      (node (ref "IC19") (pin "3") (pinfunction "NC1_3") (pintype "bidirectional"))
    )
    (net (code "70") (name "unconnected-(IC19-NC2-Pad4)") (class "Default")
      (node (ref "IC19") (pin "4") (pinfunction "NC2_4") (pintype "bidirectional"))
    )
  )
)
